# mayfly_peripheral_revb.net
KiCad netlist of a schematic drawn in EAGLE
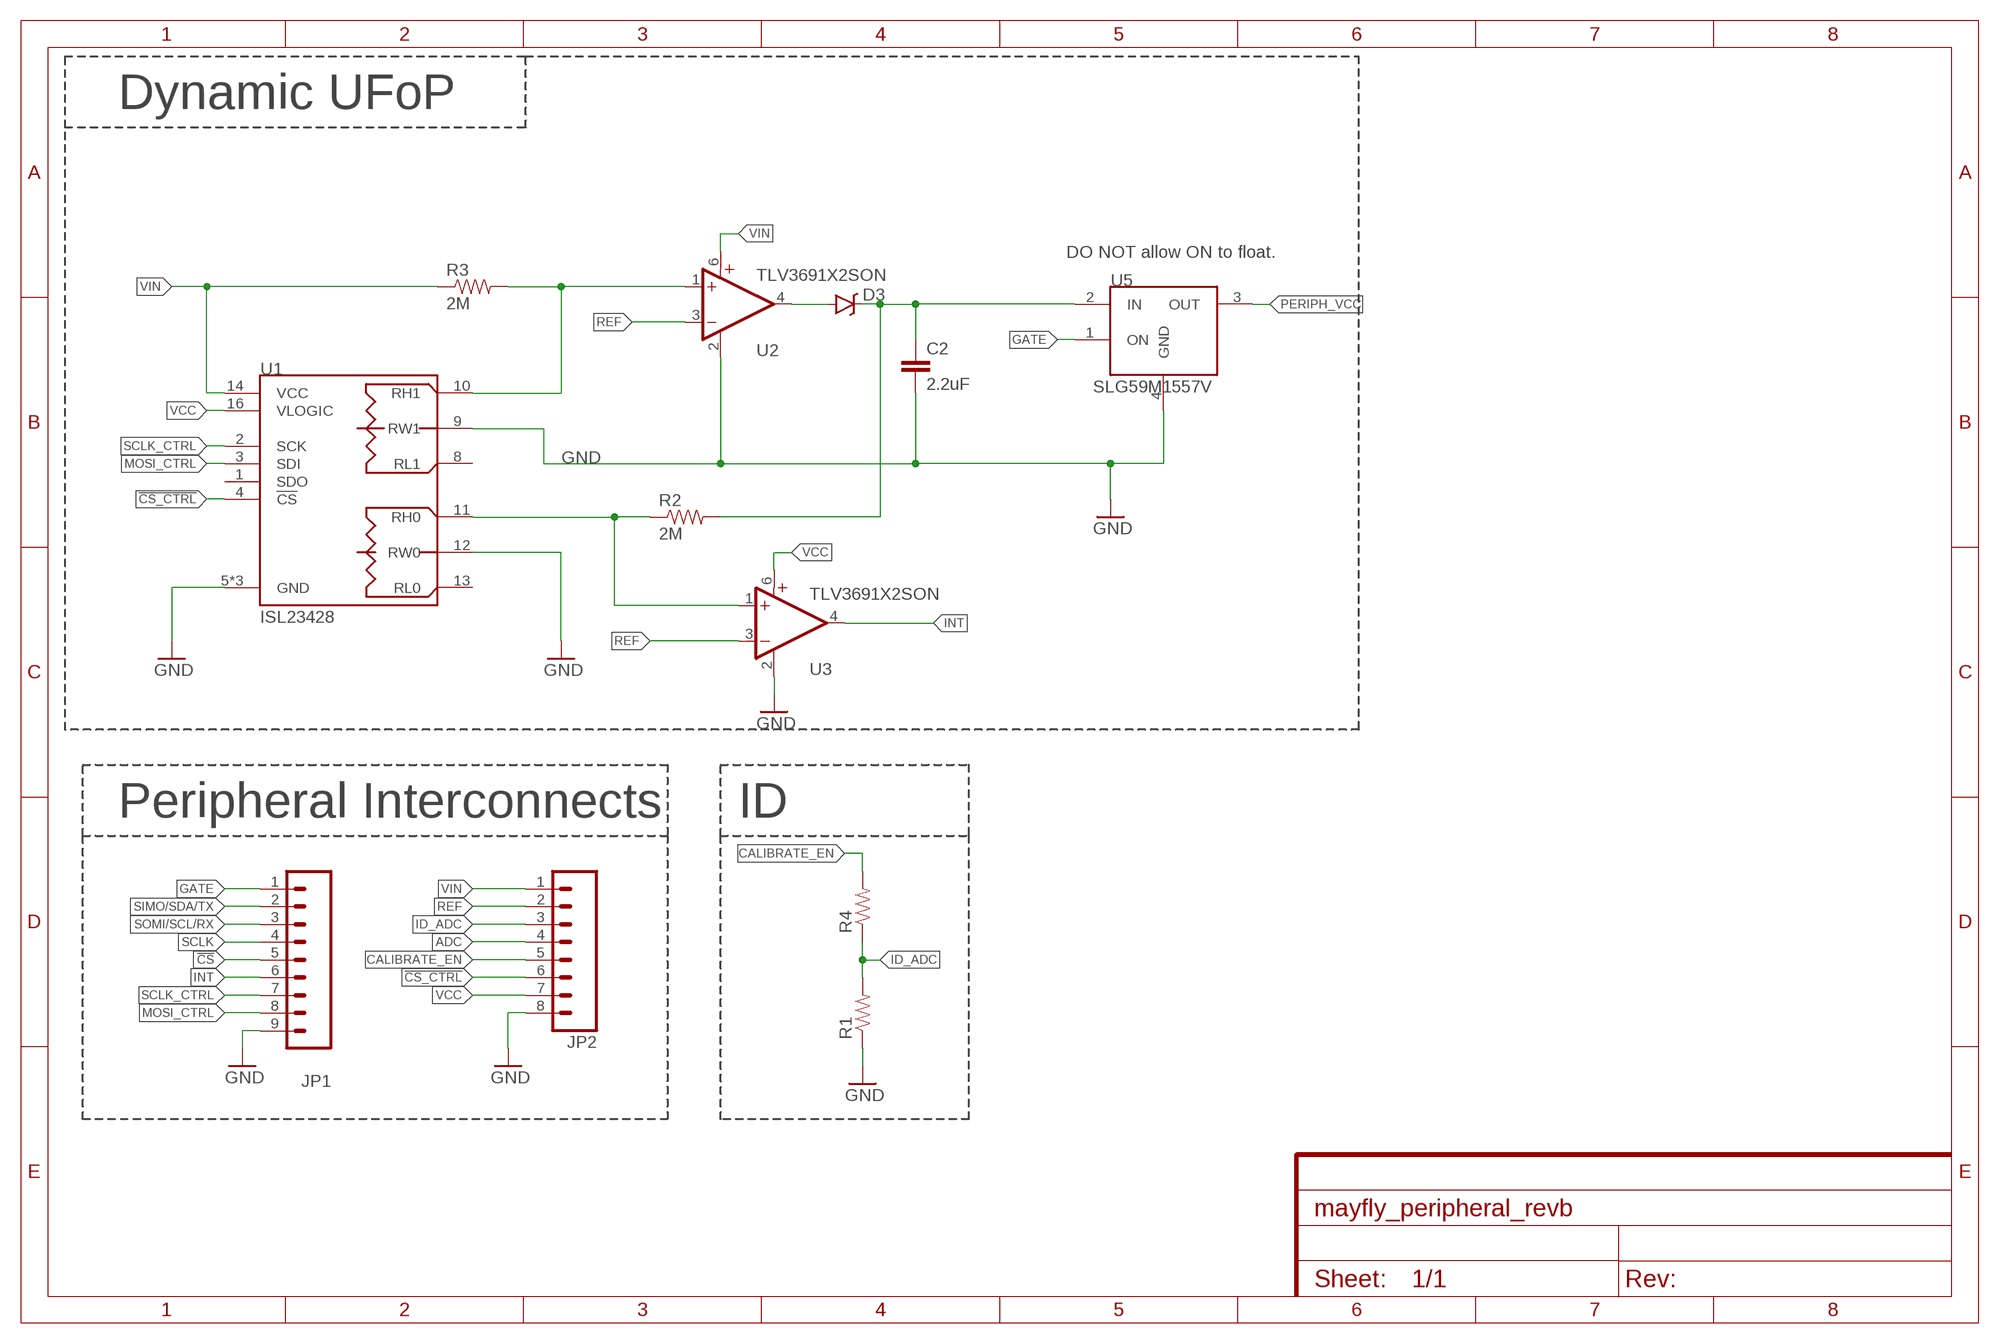
[diagram p0: schematic, sheet 1]

(export (version "E")
  (design (tool "Eeschema 10.0.6"))
  (components
    (comp (ref "C2")
      (value "2.2uF")
      (footprint "eagle-import:0603")
      (libsource (lib "eagle-import") (part "C-EU0603"))
    )
    (comp (ref "D3")
      (value "RB751")
      (footprint "eagle-import:SOD-523")
      (libsource (lib "eagle-import") (part "DIODE-SCHOTTKY-RB751"))
    )
    (comp (ref "JP1")
      (value "M091.27MM")
      (footprint "eagle-import:1X09-1.27MM")
      (fields (field (name "MANUFACTURERPARTNUMBER") "GRPB091VWVN-RC "))
      (libsource (lib "eagle-import") (part "M091.27MM"))
    )
    (comp (ref "JP2")
      (value "M081.27MM")
      (footprint "eagle-import:1X08-1.27MM")
      (fields (field (name "MANUFACTURERPARTNUMBER") "GRPB081VWVN-RC "))
      (libsource (lib "eagle-import") (part "M081.27MM"))
    )
    (comp (ref "R1")
      (value "R-EU")
      (footprint "eagle-import:0402")
      (libsource (lib "eagle-import") (part "R-EU"))
    )
    (comp (ref "R2")
      (value "2M")
      (footprint "eagle-import:0402")
      (libsource (lib "eagle-import") (part "R-EU"))
    )
    (comp (ref "R3")
      (value "2M")
      (footprint "eagle-import:0402")
      (libsource (lib "eagle-import") (part "R-EU"))
    )
    (comp (ref "R4")
      (value "R-EU")
      (footprint "eagle-import:0402")
      (libsource (lib "eagle-import") (part "R-EU"))
    )
    (comp (ref "U1")
      (value "ISL23428")
      (footprint "eagle-import:UTQFN-16")
      (libsource (lib "eagle-import") (part "ISL23428"))
    )
    (comp (ref "U2")
      (value "TLV3691X2SON")
      (footprint "eagle-import:X2SON")
      (libsource (lib "eagle-import") (part "TLV3691X2SON"))
    )
    (comp (ref "U3")
      (value "TLV3691X2SON")
      (footprint "eagle-import:X2SON")
      (libsource (lib "eagle-import") (part "TLV3691X2SON"))
    )
    (comp (ref "U5")
      (value "SLG59M1557V")
      (footprint "eagle-import:4STDFN")
      (libsource (lib "eagle-import") (part "SLG59M1557V"))
    )
  )
  (nets
    (net (code "1") (name "/~{CS_CTRL}") (class "Default")
      (node (ref "JP2") (pin "6") (pinfunction "6_6") (pintype "passive"))
      (node (ref "U1") (pin "4") (pinfunction "~{CS}_4") (pintype "bidirectional"))
    )
    (net (code "2") (name "/~{CS}") (class "Default")
      (node (ref "JP1") (pin "5") (pinfunction "5_5") (pintype "passive"))
    )
    (net (code "3") (name "ADC") (class "Default")
      (node (ref "JP2") (pin "4") (pinfunction "4_4") (pintype "passive"))
    )
    (net (code "4") (name "CALIBRATE_EN") (class "Default")
      (node (ref "JP2") (pin "5") (pinfunction "5_5") (pintype "passive"))
      (node (ref "R4") (pin "2") (pinfunction "2_2") (pintype "passive"))
    )
    (net (code "5") (name "GATE") (class "Default")
      (node (ref "JP1") (pin "1") (pinfunction "1_1") (pintype "passive"))
      (node (ref "U5") (pin "1") (pinfunction "ON_1") (pintype "bidirectional"))
    )
    (net (code "6") (name "GND") (class "Default")
      (node (ref "C2") (pin "2") (pinfunction "2_2") (pintype "passive"))
      (node (ref "JP1") (pin "9") (pinfunction "9_9") (pintype "passive"))
      (node (ref "JP2") (pin "8") (pinfunction "8_8") (pintype "passive"))
      (node (ref "R1") (pin "1") (pinfunction "1_1") (pintype "passive"))
      (node (ref "U1") (pin "12") (pinfunction "RW0_12") (pintype "bidirectional"))
      (node (ref "U1") (pin "15") (pinfunction "GND_15") (pintype "bidirectional"))
      (node (ref "U1") (pin "5") (pinfunction "GND_5") (pintype "bidirectional"))
      (node (ref "U1") (pin "6") (pinfunction "GND_6") (pintype "bidirectional"))
      (node (ref "U1") (pin "9") (pinfunction "RW1_9") (pintype "bidirectional"))
      (node (ref "U2") (pin "2") (pinfunction "GND_2") (pintype "power_in"))
      (node (ref "U3") (pin "2") (pinfunction "GND_2") (pintype "power_in"))
      (node (ref "U5") (pin "4") (pinfunction "GND_4") (pintype "bidirectional"))
    )
    (net (code "7") (name "ID_ADC") (class "Default")
      (node (ref "JP2") (pin "3") (pinfunction "3_3") (pintype "passive"))
      (node (ref "R1") (pin "2") (pinfunction "2_2") (pintype "passive"))
      (node (ref "R4") (pin "1") (pinfunction "1_1") (pintype "passive"))
    )
    (net (code "8") (name "INT") (class "Default")
      (node (ref "JP1") (pin "6") (pinfunction "6_6") (pintype "passive"))
      (node (ref "U3") (pin "4") (pinfunction "OUT_4") (pintype "output"))
    )
    (net (code "9") (name "MOSI_CTRL") (class "Default")
      (node (ref "JP1") (pin "8") (pinfunction "8_8") (pintype "passive"))
      (node (ref "U1") (pin "3") (pinfunction "SDI_3") (pintype "bidirectional"))
    )
    (net (code "10") (name "Net-(U1-RH0)") (class "Default")
      (node (ref "R2") (pin "1") (pinfunction "1_1") (pintype "passive"))
      (node (ref "U1") (pin "11") (pinfunction "RH0_11") (pintype "bidirectional"))
      (node (ref "U3") (pin "1") (pinfunction "+IN_1") (pintype "input"))
    )
    (net (code "11") (name "Net-(U1-RH1)") (class "Default")
      (node (ref "R3") (pin "2") (pinfunction "2_2") (pintype "passive"))
      (node (ref "U1") (pin "10") (pinfunction "RH1_10") (pintype "bidirectional"))
      (node (ref "U2") (pin "1") (pinfunction "+IN_1") (pintype "input"))
    )
    (net (code "12") (name "Net-(U2-OUT)") (class "Default")
      (node (ref "D3") (pin "A") (pinfunction "A_A") (pintype "passive"))
      (node (ref "U2") (pin "4") (pinfunction "OUT_4") (pintype "output"))
    )
    (net (code "13") (name "Net-(U5-IN)") (class "Default")
      (node (ref "C2") (pin "1") (pinfunction "1_1") (pintype "passive"))
      (node (ref "D3") (pin "C") (pinfunction "C_C") (pintype "passive"))
      (node (ref "R2") (pin "2") (pinfunction "2_2") (pintype "passive"))
      (node (ref "U5") (pin "2") (pinfunction "IN_2") (pintype "bidirectional"))
    )
    (net (code "14") (name "PERIPH_VCC") (class "Default")
      (node (ref "U5") (pin "3") (pinfunction "OUT_3") (pintype "bidirectional"))
    )
    (net (code "15") (name "REF") (class "Default")
      (node (ref "JP2") (pin "2") (pinfunction "2_2") (pintype "passive"))
      (node (ref "U2") (pin "3") (pinfunction "-IN_3") (pintype "input"))
      (node (ref "U3") (pin "3") (pinfunction "-IN_3") (pintype "input"))
    )
    (net (code "16") (name "SCLK") (class "Default")
      (node (ref "JP1") (pin "4") (pinfunction "4_4") (pintype "passive"))
    )
    (net (code "17") (name "SCLK_CTRL") (class "Default")
      (node (ref "JP1") (pin "7") (pinfunction "7_7") (pintype "passive"))
      (node (ref "U1") (pin "2") (pinfunction "SCK_2") (pintype "bidirectional"))
    )
    (net (code "18") (name "SIMO{slash}SDA{slash}TX") (class "Default")
      (node (ref "JP1") (pin "2") (pinfunction "2_2") (pintype "passive"))
    )
    (net (code "19") (name "SOMI{slash}SCL{slash}RX") (class "Default")
      (node (ref "JP1") (pin "3") (pinfunction "3_3") (pintype "passive"))
    )
    (net (code "20") (name "VCC") (class "Default")
      (node (ref "JP2") (pin "7") (pinfunction "7_7") (pintype "passive"))
      (node (ref "U1") (pin "16") (pinfunction "VLOGIC_16") (pintype "bidirectional"))
      (node (ref "U3") (pin "6") (pinfunction "V+_6") (pintype "power_in"))
    )
    (net (code "21") (name "VIN") (class "Default")
      (node (ref "JP2") (pin "1") (pinfunction "1_1") (pintype "passive"))
      (node (ref "R3") (pin "1") (pinfunction "1_1") (pintype "passive"))
      (node (ref "U1") (pin "14") (pinfunction "VCC_14") (pintype "bidirectional"))
      (node (ref "U2") (pin "6") (pinfunction "V+_6") (pintype "power_in"))
    )
    (net (code "22") (name "unconnected-(U1-RL0-Pad13)") (class "Default")
      (node (ref "U1") (pin "13") (pinfunction "RL0_13") (pintype "bidirectional"))
    )
    (net (code "23") (name "unconnected-(U1-RL1-Pad8)") (class "Default")
      (node (ref "U1") (pin "8") (pinfunction "RL1_8") (pintype "bidirectional"))
    )
    (net (code "24") (name "unconnected-(U1-SDO-Pad1)") (class "Default")
      (node (ref "U1") (pin "1") (pinfunction "SDO_1") (pintype "bidirectional"))
    )
  )
)
